# CVTOP.net
KiCad netlist of a schematic drawn in Altium Designer
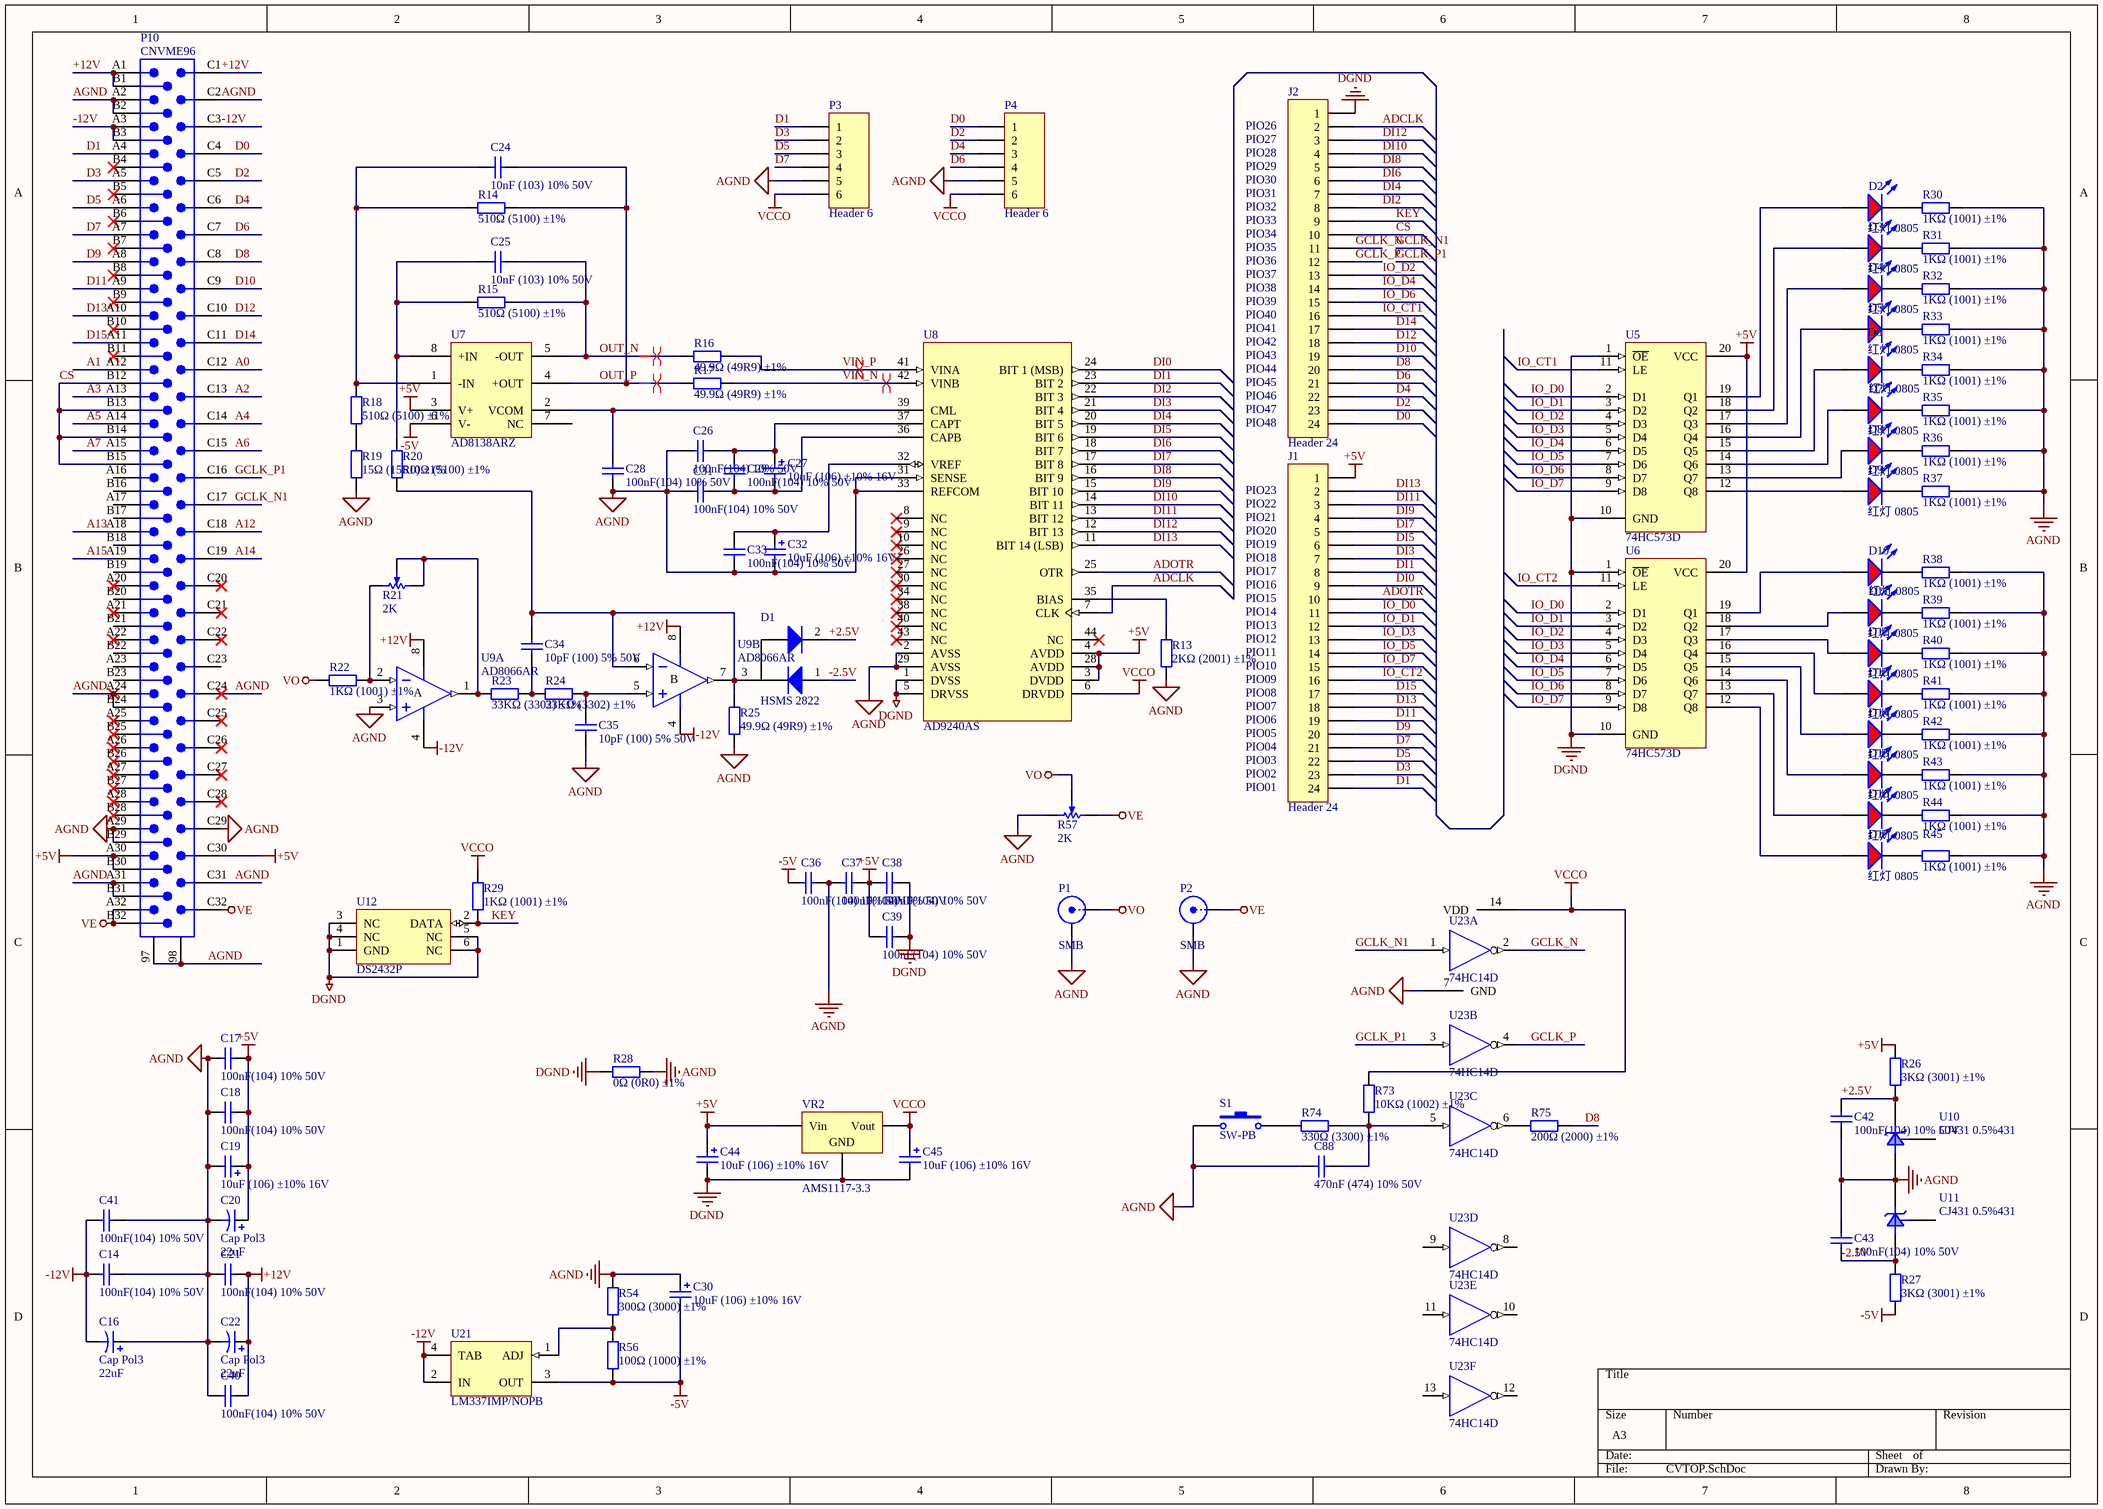
[diagram p0: CVTOP.SchDoc]

(export (version "E")
  (design (tool "Eeschema 10.0.6"))
  (components
    (comp (ref "C14")
      (value "100nF(104) 10% 50V")
      (footprint "LC-0805_C")
      (description "贴片电容")
      (libsource (lib "Miscellaneous Devices LC") (part "0805 100nF(104) 10% 50V"))
    )
    (comp (ref "C16")
      (value "Cap Pol3")
      (footprint "C2225")
      (description "Polarized Capacitor (Surface Mount)")
      (fields (field (name "ALTIUM_VALUE") "22uF") (field (name "PUBLISHER") "Altium Limited"))
      (libsource (lib "Miscellaneous Devices") (part "Cap Pol3"))
    )
    (comp (ref "C17")
      (value "100nF(104) 10% 50V")
      (footprint "LC-0805_C")
      (description "贴片电容")
      (libsource (lib "Miscellaneous Devices LC") (part "0805 100nF(104) 10% 50V"))
    )
    (comp (ref "C18")
      (value "100nF(104) 10% 50V")
      (footprint "LC-0805_C")
      (description "贴片电容")
      (libsource (lib "Miscellaneous Devices LC") (part "0805 100nF(104) 10% 50V"))
    )
    (comp (ref "C19")
      (value "10uF (106) ±10% 16V")
      (footprint "LC-CASE-A_3216")
      (description "钽电容")
      (libsource (lib "Miscellaneous Devices LC") (part "3216 10uF (106) 10% 16V"))
    )
    (comp (ref "C20")
      (value "Cap Pol3")
      (footprint "C2225")
      (description "Polarized Capacitor (Surface Mount)")
      (fields (field (name "ALTIUM_VALUE") "22uF") (field (name "PUBLISHER") "Altium Limited"))
      (libsource (lib "Miscellaneous Devices") (part "Cap Pol3"))
    )
    (comp (ref "C21")
      (value "100nF(104) 10% 50V")
      (footprint "LC-0805_C")
      (description "贴片电容")
      (libsource (lib "Miscellaneous Devices LC") (part "0805 100nF(104) 10% 50V"))
    )
    (comp (ref "C22")
      (value "Cap Pol3")
      (footprint "C2225")
      (description "Polarized Capacitor (Surface Mount)")
      (fields (field (name "ALTIUM_VALUE") "22uF") (field (name "PUBLISHER") "Altium Limited"))
      (libsource (lib "Miscellaneous Devices") (part "Cap Pol3"))
    )
    (comp (ref "C24")
      (value "10nF (103) 10% 50V")
      (footprint "LC-0805_C")
      (description "贴片电容")
      (libsource (lib "Miscellaneous Devices LC") (part "0805 10nF (103) 10% 50V"))
    )
    (comp (ref "C25")
      (value "10nF (103) 10% 50V")
      (footprint "LC-0805_C")
      (description "贴片电容")
      (libsource (lib "Miscellaneous Devices LC") (part "0805 10nF (103) 10% 50V"))
    )
    (comp (ref "C26")
      (value "100nF(104) 10% 50V")
      (footprint "LC-0805_C")
      (description "贴片电容")
      (libsource (lib "Miscellaneous Devices LC") (part "0805 100nF(104) 10% 50V"))
    )
    (comp (ref "C27")
      (value "10uF (106) ±10% 16V")
      (footprint "LC-CASE-A_3216")
      (description "钽电容")
      (libsource (lib "Miscellaneous Devices LC") (part "3216 10uF (106) 10% 16V"))
    )
    (comp (ref "C28")
      (value "100nF(104) 10% 50V")
      (footprint "LC-0805_C")
      (description "贴片电容")
      (libsource (lib "Miscellaneous Devices LC") (part "0805 100nF(104) 10% 50V"))
    )
    (comp (ref "C29")
      (value "100nF(104) 10% 50V")
      (footprint "LC-0805_C")
      (description "贴片电容")
      (libsource (lib "Miscellaneous Devices LC") (part "0805 100nF(104) 10% 50V"))
    )
    (comp (ref "C30")
      (value "10uF (106) ±10% 16V")
      (footprint "LC-CASE-A_3216")
      (description "钽电容")
      (libsource (lib "Miscellaneous Devices LC") (part "3216 10uF (106) 10% 16V"))
    )
    (comp (ref "C31")
      (value "100nF(104) 10% 50V")
      (footprint "LC-0805_C")
      (description "贴片电容")
      (libsource (lib "Miscellaneous Devices LC") (part "0805 100nF(104) 10% 50V"))
    )
    (comp (ref "C32")
      (value "10uF (106) ±10% 16V")
      (footprint "LC-CASE-A_3216")
      (description "钽电容")
      (libsource (lib "Miscellaneous Devices LC") (part "3216 10uF (106) 10% 16V"))
    )
    (comp (ref "C33")
      (value "100nF(104) 10% 50V")
      (footprint "LC-0805_C")
      (description "贴片电容")
      (libsource (lib "Miscellaneous Devices LC") (part "0805 100nF(104) 10% 50V"))
    )
    (comp (ref "C34")
      (value "10pF (100) 5% 50V")
      (footprint "LC-0805_C")
      (description "贴片电容")
      (libsource (lib "Miscellaneous Devices LC") (part "0805 10pF (100) 5% 50V"))
    )
    (comp (ref "C35")
      (value "10pF (100) 5% 50V")
      (footprint "LC-0805_C")
      (description "贴片电容")
      (libsource (lib "Miscellaneous Devices LC") (part "0805 10pF (100) 5% 50V"))
    )
    (comp (ref "C36")
      (value "100nF(104) 10% 50V")
      (footprint "LC-0805_C")
      (description "贴片电容")
      (libsource (lib "Miscellaneous Devices LC") (part "0805 100nF(104) 10% 50V"))
    )
    (comp (ref "C37")
      (value "100nF(104) 10% 50V")
      (footprint "LC-0805_C")
      (description "贴片电容")
      (libsource (lib "Miscellaneous Devices LC") (part "0805 100nF(104) 10% 50V"))
    )
    (comp (ref "C38")
      (value "100nF(104) 10% 50V")
      (footprint "LC-0805_C")
      (description "贴片电容")
      (libsource (lib "Miscellaneous Devices LC") (part "0805 100nF(104) 10% 50V"))
    )
    (comp (ref "C39")
      (value "100nF(104) 10% 50V")
      (footprint "LC-0805_C")
      (description "贴片电容")
      (libsource (lib "Miscellaneous Devices LC") (part "0805 100nF(104) 10% 50V"))
    )
    (comp (ref "C40")
      (value "100nF(104) 10% 50V")
      (footprint "LC-0805_C")
      (description "贴片电容")
      (libsource (lib "Miscellaneous Devices LC") (part "0805 100nF(104) 10% 50V"))
    )
    (comp (ref "C41")
      (value "100nF(104) 10% 50V")
      (footprint "LC-0805_C")
      (description "贴片电容")
      (libsource (lib "Miscellaneous Devices LC") (part "0805 100nF(104) 10% 50V"))
    )
    (comp (ref "C42")
      (value "100nF(104) 10% 50V")
      (footprint "LC-0805_C")
      (description "贴片电容")
      (libsource (lib "Miscellaneous Devices LC") (part "0805 100nF(104) 10% 50V"))
    )
    (comp (ref "C43")
      (value "100nF(104) 10% 50V")
      (footprint "LC-0805_C")
      (description "贴片电容")
      (libsource (lib "Miscellaneous Devices LC") (part "0805 100nF(104) 10% 50V"))
    )
    (comp (ref "C44")
      (value "10uF (106) ±10% 16V")
      (footprint "LC-CASE-A_3216")
      (description "钽电容")
      (libsource (lib "Miscellaneous Devices LC") (part "3216 10uF (106) 10% 16V"))
    )
    (comp (ref "C45")
      (value "10uF (106) ±10% 16V")
      (footprint "LC-CASE-A_3216")
      (description "钽电容")
      (libsource (lib "Miscellaneous Devices LC") (part "3216 10uF (106) 10% 16V"))
    )
    (comp (ref "C88")
      (value "470nF (474) 10% 50V")
      (footprint "LC-0805_C")
      (description "贴片电容")
      (libsource (lib "Miscellaneous Devices LC") (part "0805 470nF (474) 10% 50V"))
    )
    (comp (ref "D1")
      (value "HSMS 2822")
      (footprint "LC-SOT-23(SOT-23-3)")
      (description "开关二极管")
      (libsource (lib "Miscellaneous Devices LC") (part "SOT-23 BAV99 A7W"))
    )
    (comp (ref "D2")
      (value "红灯 0805")
      (footprint "LC-0805_LED_S1")
      (description "发光二极管")
      (libsource (lib "Miscellaneous Devices LC") (part "0805 红灯"))
    )
    (comp (ref "D3")
      (value "红灯 0805")
      (footprint "LC-0805_LED_S1")
      (description "发光二极管")
      (libsource (lib "Miscellaneous Devices LC") (part "0805 红灯"))
    )
    (comp (ref "D4")
      (value "红灯 0805")
      (footprint "LC-0805_LED_S1")
      (description "发光二极管")
      (libsource (lib "Miscellaneous Devices LC") (part "0805 红灯"))
    )
    (comp (ref "D5")
      (value "红灯 0805")
      (footprint "LC-0805_LED_S1")
      (description "发光二极管")
      (libsource (lib "Miscellaneous Devices LC") (part "0805 红灯"))
    )
    (comp (ref "D6")
      (value "红灯 0805")
      (footprint "LC-0805_LED_S1")
      (description "发光二极管")
      (libsource (lib "Miscellaneous Devices LC") (part "0805 红灯"))
    )
    (comp (ref "D7")
      (value "红灯 0805")
      (footprint "LC-0805_LED_S1")
      (description "发光二极管")
      (libsource (lib "Miscellaneous Devices LC") (part "0805 红灯"))
    )
    (comp (ref "D8")
      (value "红灯 0805")
      (footprint "LC-0805_LED_S1")
      (description "发光二极管")
      (libsource (lib "Miscellaneous Devices LC") (part "0805 红灯"))
    )
    (comp (ref "D9")
      (value "红灯 0805")
      (footprint "LC-0805_LED_S1")
      (description "发光二极管")
      (libsource (lib "Miscellaneous Devices LC") (part "0805 红灯"))
    )
    (comp (ref "D10")
      (value "红灯 0805")
      (footprint "LC-0805_LED_S1")
      (description "发光二极管")
      (libsource (lib "Miscellaneous Devices LC") (part "0805 红灯"))
    )
    (comp (ref "D11")
      (value "红灯 0805")
      (footprint "LC-0805_LED_S1")
      (description "发光二极管")
      (libsource (lib "Miscellaneous Devices LC") (part "0805 红灯"))
    )
    (comp (ref "D12")
      (value "红灯 0805")
      (footprint "LC-0805_LED_S1")
      (description "发光二极管")
      (libsource (lib "Miscellaneous Devices LC") (part "0805 红灯"))
    )
    (comp (ref "D13")
      (value "红灯 0805")
      (footprint "LC-0805_LED_S1")
      (description "发光二极管")
      (libsource (lib "Miscellaneous Devices LC") (part "0805 红灯"))
    )
    (comp (ref "D14")
      (value "红灯 0805")
      (footprint "LC-0805_LED_S1")
      (description "发光二极管")
      (libsource (lib "Miscellaneous Devices LC") (part "0805 红灯"))
    )
    (comp (ref "D15")
      (value "红灯 0805")
      (footprint "LC-0805_LED_S1")
      (description "发光二极管")
      (libsource (lib "Miscellaneous Devices LC") (part "0805 红灯"))
    )
    (comp (ref "D16")
      (value "红灯 0805")
      (footprint "LC-0805_LED_S1")
      (description "发光二极管")
      (libsource (lib "Miscellaneous Devices LC") (part "0805 红灯"))
    )
    (comp (ref "D17")
      (value "红灯 0805")
      (footprint "LC-0805_LED_S1")
      (description "发光二极管")
      (libsource (lib "Miscellaneous Devices LC") (part "0805 红灯"))
    )
    (comp (ref "J1")
      (value "Header 24")
      (footprint "HDR1X24")
      (description "Header, 24-Pin")
      (fields (field (name "PUBLISHER") "Altium Limited"))
      (libsource (lib "Miscellaneous Connectors") (part "Header 24"))
    )
    (comp (ref "J2")
      (value "Header 24")
      (footprint "HDR1X24")
      (description "Header, 24-Pin")
      (fields (field (name "PUBLISHER") "Altium Limited"))
      (libsource (lib "Miscellaneous Connectors") (part "Header 24"))
    )
    (comp (ref "P1")
      (value "SMB")
      (footprint "SMB_V-RJ45")
      (description "SMB Straight Connector")
      (fields (field (name "PUBLISHER") "Altium Limited"))
      (libsource (lib "Miscellaneous Connectors") (part "SMB"))
    )
    (comp (ref "P2")
      (value "SMB")
      (footprint "SMB_V-RJ45")
      (description "SMB Straight Connector")
      (fields (field (name "PUBLISHER") "Altium Limited"))
      (libsource (lib "Miscellaneous Connectors") (part "SMB"))
    )
    (comp (ref "P3")
      (value "Header 6")
      (footprint "HDR1X6")
      (description "Header, 6-Pin")
      (fields (field (name "PUBLISHER") "Altium Limited"))
      (libsource (lib "Miscellaneous Connectors") (part "Header 6"))
    )
    (comp (ref "P4")
      (value "Header 6")
      (footprint "HDR1X6")
      (description "Header, 6-Pin")
      (fields (field (name "PUBLISHER") "Altium Limited"))
      (libsource (lib "Miscellaneous Connectors") (part "Header 6"))
    )
    (comp (ref "P10")
      (value "CNVME96")
      (footprint "CNVME96")
      (description "96-Pin Connector (3x32 2.54mm grid)")
      (libsource (lib "*") (part "CNVME96"))
    )
    (comp (ref "R13")
      (value "2KΩ (2001) ±1%")
      (footprint "LC-0805_R")
      (description "贴片电阻")
      (libsource (lib "Miscellaneous Devices LC") (part "0805 2KΩ (2001) 1%"))
    )
    (comp (ref "R14")
      (value "510Ω (5100) ±1%")
      (footprint "LC-0805_R")
      (description "贴片电阻")
      (libsource (lib "Miscellaneous Devices LC") (part "0805 510Ω (5100) 1%"))
    )
    (comp (ref "R15")
      (value "510Ω (5100) ±1%")
      (footprint "LC-0805_R")
      (description "贴片电阻")
      (libsource (lib "Miscellaneous Devices LC") (part "0805 510Ω (5100) 1%"))
    )
    (comp (ref "R16")
      (value "49.9Ω (49R9) ±1%")
      (footprint "LC-0805_R")
      (description "贴片电阻")
      (libsource (lib "Miscellaneous Devices LC") (part "0805 49.9Ω (49R9) 1%"))
    )
    (comp (ref "R17")
      (value "49.9Ω (49R9) ±1%")
      (footprint "LC-0805_R")
      (description "贴片电阻")
      (libsource (lib "Miscellaneous Devices LC") (part "0805 49.9Ω (49R9) 1%"))
    )
    (comp (ref "R18")
      (value "510Ω (5100) ±1%")
      (footprint "LC-0805_R")
      (description "贴片电阻")
      (libsource (lib "") (part "0805 510Ω (5100) 1%_1"))
    )
    (comp (ref "R19")
      (value "15Ω (15R0) ±1%")
      (footprint "LC-0805_R")
      (description "贴片电阻")
      (libsource (lib "Miscellaneous Devices LC") (part "0805 15Ω (15R0) 1%"))
    )
    (comp (ref "R20")
      (value "510Ω (5100) ±1%")
      (footprint "LC-0805_R")
      (description "贴片电阻")
      (libsource (lib "") (part "0805 510Ω (5100) 1%_1"))
    )
    (comp (ref "R21")
      (value "2K")
      (footprint "POT4MM-2")
      (description "Square Trimming Potentiometer")
      (fields (field (name "PUBLISHER") "Altium Limited"))
      (libsource (lib "Miscellaneous Devices") (part "RPot SM"))
    )
    (comp (ref "R22")
      (value "1KΩ (1001) ±1%")
      (footprint "LC-0805_R")
      (description "贴片电阻")
      (libsource (lib "Miscellaneous Devices LC") (part "0805 1KΩ (1001) 1%"))
    )
    (comp (ref "R23")
      (value "33KΩ (3302) ±1%")
      (footprint "LC-0805_R")
      (description "贴片电阻")
      (libsource (lib "Miscellaneous Devices LC") (part "0805 33KΩ (3302) 1%"))
    )
    (comp (ref "R24")
      (value "33KΩ (3302) ±1%")
      (footprint "LC-0805_R")
      (description "贴片电阻")
      (libsource (lib "Miscellaneous Devices LC") (part "0805 33KΩ (3302) 1%"))
    )
    (comp (ref "R25")
      (value "49.9Ω (49R9) ±1%")
      (footprint "LC-0805_R")
      (description "贴片电阻")
      (libsource (lib "") (part "0805 49.9Ω (49R9) 1%_1"))
    )
    (comp (ref "R26")
      (value "3KΩ (3001) ±1%")
      (footprint "LC-0805_R")
      (description "贴片电阻")
      (libsource (lib "Miscellaneous Devices LC") (part "0805 3KΩ (3001) 1%"))
    )
    (comp (ref "R27")
      (value "3KΩ (3001) ±1%")
      (footprint "LC-0805_R")
      (description "贴片电阻")
      (libsource (lib "Miscellaneous Devices LC") (part "0805 3KΩ (3001) 1%"))
    )
    (comp (ref "R28")
      (value "0Ω (0R0) ±1%")
      (footprint "LC-0805_R")
      (description "贴片电阻")
      (libsource (lib "Miscellaneous Devices LC") (part "0805 0Ω (0R0) 1%"))
    )
    (comp (ref "R29")
      (value "1KΩ (1001) ±1%")
      (footprint "LC-0805_R")
      (description "贴片电阻")
      (libsource (lib "") (part "0805 1KΩ (1001) 1%_1"))
    )
    (comp (ref "R30")
      (value "1KΩ (1001) ±1%")
      (footprint "LC-0805_R")
      (description "贴片电阻")
      (libsource (lib "Miscellaneous Devices LC") (part "0805 1KΩ (1001) 1%"))
    )
    (comp (ref "R31")
      (value "1KΩ (1001) ±1%")
      (footprint "LC-0805_R")
      (description "贴片电阻")
      (libsource (lib "Miscellaneous Devices LC") (part "0805 1KΩ (1001) 1%"))
    )
    (comp (ref "R32")
      (value "1KΩ (1001) ±1%")
      (footprint "LC-0805_R")
      (description "贴片电阻")
      (libsource (lib "Miscellaneous Devices LC") (part "0805 1KΩ (1001) 1%"))
    )
    (comp (ref "R33")
      (value "1KΩ (1001) ±1%")
      (footprint "LC-0805_R")
      (description "贴片电阻")
      (libsource (lib "Miscellaneous Devices LC") (part "0805 1KΩ (1001) 1%"))
    )
    (comp (ref "R34")
      (value "1KΩ (1001) ±1%")
      (footprint "LC-0805_R")
      (description "贴片电阻")
      (libsource (lib "Miscellaneous Devices LC") (part "0805 1KΩ (1001) 1%"))
    )
    (comp (ref "R35")
      (value "1KΩ (1001) ±1%")
      (footprint "LC-0805_R")
      (description "贴片电阻")
      (libsource (lib "Miscellaneous Devices LC") (part "0805 1KΩ (1001) 1%"))
    )
    (comp (ref "R36")
      (value "1KΩ (1001) ±1%")
      (footprint "LC-0805_R")
      (description "贴片电阻")
      (libsource (lib "Miscellaneous Devices LC") (part "0805 1KΩ (1001) 1%"))
    )
    (comp (ref "R37")
      (value "1KΩ (1001) ±1%")
      (footprint "LC-0805_R")
      (description "贴片电阻")
      (libsource (lib "Miscellaneous Devices LC") (part "0805 1KΩ (1001) 1%"))
    )
    (comp (ref "R38")
      (value "1KΩ (1001) ±1%")
      (footprint "LC-0805_R")
      (description "贴片电阻")
      (libsource (lib "Miscellaneous Devices LC") (part "0805 1KΩ (1001) 1%"))
    )
    (comp (ref "R39")
      (value "1KΩ (1001) ±1%")
      (footprint "LC-0805_R")
      (description "贴片电阻")
      (libsource (lib "Miscellaneous Devices LC") (part "0805 1KΩ (1001) 1%"))
    )
    (comp (ref "R40")
      (value "1KΩ (1001) ±1%")
      (footprint "LC-0805_R")
      (description "贴片电阻")
      (libsource (lib "Miscellaneous Devices LC") (part "0805 1KΩ (1001) 1%"))
    )
    (comp (ref "R41")
      (value "1KΩ (1001) ±1%")
      (footprint "LC-0805_R")
      (description "贴片电阻")
      (libsource (lib "Miscellaneous Devices LC") (part "0805 1KΩ (1001) 1%"))
    )
    (comp (ref "R42")
      (value "1KΩ (1001) ±1%")
      (footprint "LC-0805_R")
      (description "贴片电阻")
      (libsource (lib "Miscellaneous Devices LC") (part "0805 1KΩ (1001) 1%"))
    )
    (comp (ref "R43")
      (value "1KΩ (1001) ±1%")
      (footprint "LC-0805_R")
      (description "贴片电阻")
      (libsource (lib "Miscellaneous Devices LC") (part "0805 1KΩ (1001) 1%"))
    )
    (comp (ref "R44")
      (value "1KΩ (1001) ±1%")
      (footprint "LC-0805_R")
      (description "贴片电阻")
      (libsource (lib "Miscellaneous Devices LC") (part "0805 1KΩ (1001) 1%"))
    )
    (comp (ref "R45")
      (value "1KΩ (1001) ±1%")
      (footprint "LC-0805_R")
      (description "贴片电阻")
      (libsource (lib "Miscellaneous Devices LC") (part "0805 1KΩ (1001) 1%"))
    )
    (comp (ref "R54")
      (value "300Ω (3000) ±1%")
      (footprint "LC-0805_R")
      (description "贴片电阻")
      (libsource (lib "Miscellaneous Devices LC") (part "0805 300Ω (3000) 1%"))
    )
    (comp (ref "R56")
      (value "100Ω (1000) ±1%")
      (footprint "LC-0805_R")
      (description "贴片电阻")
      (libsource (lib "Miscellaneous Devices LC") (part "0805 100Ω (1000) 1%"))
    )
    (comp (ref "R57")
      (value "2K")
      (footprint "POT4MM-2")
      (description "Square Trimming Potentiometer")
      (fields (field (name "PUBLISHER") "Altium Limited"))
      (libsource (lib "Miscellaneous Devices") (part "RPot SM"))
    )
    (comp (ref "R73")
      (value "10KΩ (1002) ±1%")
      (footprint "LC-0805_R")
      (description "贴片电阻")
      (libsource (lib "Miscellaneous Devices LC") (part "0805 10KΩ (1002) 1%"))
    )
    (comp (ref "R74")
      (value "330Ω (3300) ±1%")
      (footprint "LC-0805_R")
      (description "贴片电阻")
      (libsource (lib "Miscellaneous Devices LC") (part "0805 330Ω (3300) 1%"))
    )
    (comp (ref "R75")
      (value "200Ω (2000) ±1%")
      (footprint "LC-0805_R")
      (description "贴片电阻")
      (libsource (lib "Miscellaneous Devices LC") (part "0805 200Ω (2000) 1%"))
    )
    (comp (ref "S1")
      (value "SW-PB")
      (footprint "SPST-2")
      (description "Switch")
      (fields (field (name "PUBLISHER") "Altium Limited"))
      (libsource (lib "Miscellaneous Devices") (part "SW-PB"))
    )
    (comp (ref "U5")
      (value "74HC573D")
      (footprint "LC-SOIC-20_300mil")
      (description "74系列逻辑芯片")
      (libsource (lib "Miscellaneous Devices LC") (part "74HC573D"))
    )
    (comp (ref "U6")
      (value "74HC573D")
      (footprint "LC-SOIC-20_300mil")
      (description "74系列逻辑芯片")
      (libsource (lib "Miscellaneous Devices LC") (part "74HC573D"))
    )
    (comp (ref "U7") (value "AD8138ARZ") (footprint "SO-8_N") (libsource (lib "AD8138") (part "AD8138ARZ")))
    (comp (ref "U8")
      (value "AD9240AS")
      (footprint "S-44-MQFP_N")
      (description "Complete 14-Bit, 10 MSPS Monolithic A/D Converter, 44-Pin MQFP, Industrial")
      (fields (field (name "PUBLISHER") "Altium Limited"))
      (libsource (lib "AD Converter Analog to Digital") (part "AD9240AS"))
    )
    (comp (ref "U9")
      (value "AD8066AR")
      (footprint "mini-ET:SO-8_N")
      (description "Low Cost, 300MHz Voltage Feedback Amplifier")
      (fields (field (name "PUBLISHER") "Altium Limited"))
      (libsource (lib "AD Operational Amplifier") (part "AD8056AR"))
    )
    (comp (ref "U10")
      (value "CJ431 0.5%431")
      (footprint "LC-SOT-23(SOT-23-3)")
      (description "电压基准")
      (libsource (lib "Miscellaneous Devices LC") (part "CJ431 0.5%431"))
    )
    (comp (ref "U11")
      (value "CJ431 0.5%431")
      (footprint "LC-SOT-23(SOT-23-3)")
      (description "电压基准")
      (libsource (lib "Miscellaneous Devices LC") (part "CJ431 0.5%431"))
    )
    (comp (ref "U12")
      (value "DS2432P")
      (footprint "TSOC6")
      (description "256-Bit 1-Wire EEPROM")
      (fields (field (name "PUBLISHER") "Altium Limited"))
      (libsource (lib "Dallas Memory EEPROM") (part "DS2430AP"))
    )
    (comp (ref "U21")
      (value "LM337IMP/NOPB")
      (footprint "MP04A_N")
      (description "3-Terminal Adjustable Negative Regulator, 4-pin SOT-223, Pb-Free")
      (fields
        (field (name "MANUFACTURER") "National Semiconductor")
        (field (name "PUBLISHER") "Altium Limited")
      )
      (libsource (lib "NSC LDO") (part "LM337IMP/NOPB"))
    )
    (comp (ref "U23")
      (value "74HC14D")
      (footprint "LC-SOIC-14_150mil")
      (description "74系列逻辑芯片")
      (libsource (lib "Miscellaneous Devices LC") (part "74HC14D_[C5605]"))
    )
    (comp (ref "VR2")
      (value "AMS1117-3.3")
      (footprint "LC-SOT-223")
      (description "低压差线性稳压(LDO)")
      (libsource (lib "Miscellaneous Devices LC") (part "SOT-223 AMS1117-3.3"))
    )
  )
  (nets
    (net (code "1") (name "+5V") (class "Default")
      (node (ref "C17") (pin "2") (pinfunction "2_2") (pintype "passive"))
      (node (ref "C18") (pin "2") (pinfunction "2_2") (pintype "passive"))
      (node (ref "C19") (pin "1") (pinfunction "1_1") (pintype "passive"))
      (node (ref "C20") (pin "1") (pinfunction "1_1") (pintype "passive"))
      (node (ref "C37") (pin "1") (pinfunction "1_1") (pintype "passive"))
      (node (ref "C38") (pin "2") (pinfunction "2_2") (pintype "passive"))
      (node (ref "C39") (pin "2") (pinfunction "2_2") (pintype "passive"))
      (node (ref "C44") (pin "1") (pinfunction "1_1") (pintype "passive"))
      (node (ref "J1") (pin "1") (pinfunction "1_1") (pintype "passive"))
      (node (ref "P10") (pin "A30") (pinfunction "A30_A30") (pintype "passive"))
      (node (ref "P10") (pin "B30") (pinfunction "B30_B30") (pintype "passive"))
      (node (ref "P10") (pin "C30") (pinfunction "C30_C30") (pintype "passive"))
      (node (ref "R26") (pin "2") (pinfunction "2_2") (pintype "passive"))
      (node (ref "U5") (pin "20") (pinfunction "VCC_20") (pintype "power_in"))
      (node (ref "U6") (pin "20") (pinfunction "VCC_20") (pintype "power_in"))
      (node (ref "U7") (pin "3") (pinfunction "V+_3") (pintype "passive"))
      (node (ref "U8") (pin "28") (pinfunction "AVDD_28") (pintype "power_in"))
      (node (ref "U8") (pin "3") (pinfunction "DVDD_3") (pintype "power_in"))
      (node (ref "U8") (pin "4") (pinfunction "AVDD_4") (pintype "power_in"))
      (node (ref "VR2") (pin "3") (pinfunction "Vin_3") (pintype "passive"))
    )
    (net (code "2") (name "+12V") (class "Default")
      (node (ref "C21") (pin "2") (pinfunction "2_2") (pintype "passive"))
      (node (ref "C22") (pin "1") (pinfunction "1_1") (pintype "passive"))
      (node (ref "C40") (pin "1") (pinfunction "1_1") (pintype "passive"))
      (node (ref "P10") (pin "A1") (pinfunction "A1_A1") (pintype "passive"))
      (node (ref "P10") (pin "B1") (pinfunction "B1_B1") (pintype "passive"))
      (node (ref "P10") (pin "C1") (pinfunction "C1_C1") (pintype "passive"))
      (node (ref "U9") (pin "8") (pinfunction "V+_8") (pintype "power_in"))
    )
    (net (code "3") (name "-5V") (class "Default")
      (node (ref "C30") (pin "2") (pinfunction "2_2") (pintype "passive"))
      (node (ref "C36") (pin "2") (pinfunction "2_2") (pintype "passive"))
      (node (ref "R27") (pin "1") (pinfunction "1_1") (pintype "passive"))
      (node (ref "R56") (pin "1") (pinfunction "1_1") (pintype "passive"))
      (node (ref "U21") (pin "3") (pinfunction "OUT_3") (pintype "power_in"))
      (node (ref "U7") (pin "6") (pinfunction "V-_6") (pintype "passive"))
    )
    (net (code "4") (name "-12V") (class "Default")
      (node (ref "C14") (pin "1") (pinfunction "1_1") (pintype "passive"))
      (node (ref "C16") (pin "2") (pinfunction "2_2") (pintype "passive"))
      (node (ref "C41") (pin "2") (pinfunction "2_2") (pintype "passive"))
      (node (ref "P10") (pin "A3") (pinfunction "A3_A3") (pintype "passive"))
      (node (ref "P10") (pin "B3") (pinfunction "B3_B3") (pintype "passive"))
      (node (ref "P10") (pin "C3") (pinfunction "C3_C3") (pintype "passive"))
      (node (ref "U21") (pin "2") (pinfunction "IN_2") (pintype "power_in"))
      (node (ref "U21") (pin "4") (pinfunction "TAB_4") (pintype "power_in"))
      (node (ref "U9") (pin "4") (pinfunction "V-_4") (pintype "power_in"))
    )
    (net (code "5") (name "/+2.5V") (class "Default")
      (node (ref "C42") (pin "1") (pinfunction "1_1") (pintype "passive"))
      (node (ref "D1") (pin "2") (pinfunction "A_2") (pintype "passive"))
      (node (ref "R26") (pin "1") (pinfunction "1_1") (pintype "passive"))
      (node (ref "U10") (pin "2") (pinfunction "K_2") (pintype "passive"))
    )
    (net (code "6") (name "/-2.5V") (class "Default")
      (node (ref "C43") (pin "2") (pinfunction "2_2") (pintype "passive"))
      (node (ref "D1") (pin "1") (pinfunction "A_1") (pintype "passive"))
      (node (ref "R27") (pin "2") (pinfunction "2_2") (pintype "passive"))
      (node (ref "U11") (pin "3") (pinfunction "A_3") (pintype "passive"))
    )
    (net (code "7") (name "/A0") (class "Default")
      (node (ref "P10") (pin "C12") (pinfunction "C12_C12") (pintype "passive"))
    )
    (net (code "8") (name "/A1") (class "Default")
      (node (ref "P10") (pin "A12") (pinfunction "A12_A12") (pintype "passive"))
    )
    (net (code "9") (name "/A2") (class "Default")
      (node (ref "P10") (pin "C13") (pinfunction "C13_C13") (pintype "passive"))
    )
    (net (code "10") (name "/A3") (class "Default")
      (node (ref "P10") (pin "A13") (pinfunction "A13_A13") (pintype "passive"))
    )
    (net (code "11") (name "/A4") (class "Default")
      (node (ref "P10") (pin "C14") (pinfunction "C14_C14") (pintype "passive"))
    )
    (net (code "12") (name "/A5") (class "Default")
      (node (ref "P10") (pin "A14") (pinfunction "A14_A14") (pintype "passive"))
    )
    (net (code "13") (name "/A6") (class "Default")
      (node (ref "P10") (pin "C15") (pinfunction "C15_C15") (pintype "passive"))
    )
    (net (code "14") (name "/A7") (class "Default")
      (node (ref "P10") (pin "A15") (pinfunction "A15_A15") (pintype "passive"))
    )
    (net (code "15") (name "/A12") (class "Default")
      (node (ref "P10") (pin "C18") (pinfunction "C18_C18") (pintype "passive"))
    )
    (net (code "16") (name "/A13") (class "Default")
      (node (ref "P10") (pin "A18") (pinfunction "A18_A18") (pintype "passive"))
    )
    (net (code "17") (name "/A14") (class "Default")
      (node (ref "P10") (pin "C19") (pinfunction "C19_C19") (pintype "passive"))
    )
    (net (code "18") (name "/A15") (class "Default")
      (node (ref "P10") (pin "A19") (pinfunction "A19_A19") (pintype "passive"))
    )
    (net (code "19") (name "/ADCLK") (class "Default")
      (node (ref "J2") (pin "2") (pinfunction "2_2") (pintype "passive"))
      (node (ref "U8") (pin "7") (pinfunction "CLK_7") (pintype "input"))
    )
    (net (code "20") (name "/ADOTR") (class "Default")
      (node (ref "J1") (pin "10") (pinfunction "10_10") (pintype "passive"))
      (node (ref "U8") (pin "25") (pinfunction "OTR_25") (pintype "output"))
    )
    (net (code "21") (name "/CS") (class "Default")
      (node (ref "J2") (pin "10") (pinfunction "10_10") (pintype "passive"))
      (node (ref "P10") (pin "B12") (pinfunction "B12_B12") (pintype "passive"))
      (node (ref "P10") (pin "B13") (pinfunction "B13_B13") (pintype "passive"))
      (node (ref "P10") (pin "B14") (pinfunction "B14_B14") (pintype "passive"))
      (node (ref "P10") (pin "B15") (pinfunction "B15_B15") (pintype "passive"))
    )
    (net (code "22") (name "/D0") (class "Default")
      (node (ref "J2") (pin "24") (pinfunction "24_24") (pintype "passive"))
      (node (ref "P10") (pin "C4") (pinfunction "C4_C4") (pintype "passive"))
      (node (ref "P4") (pin "1") (pinfunction "1_1") (pintype "passive"))
    )
    (net (code "23") (name "/D1") (class "Default")
      (node (ref "J1") (pin "24") (pinfunction "24_24") (pintype "passive"))
      (node (ref "P10") (pin "A4") (pinfunction "A4_A4") (pintype "passive"))
      (node (ref "P3") (pin "1") (pinfunction "1_1") (pintype "passive"))
    )
    (net (code "24") (name "/D2") (class "Default")
      (node (ref "J2") (pin "23") (pinfunction "23_23") (pintype "passive"))
      (node (ref "P10") (pin "C5") (pinfunction "C5_C5") (pintype "passive"))
      (node (ref "P4") (pin "2") (pinfunction "2_2") (pintype "passive"))
    )
    (net (code "25") (name "/D3") (class "Default")
      (node (ref "J1") (pin "23") (pinfunction "23_23") (pintype "passive"))
      (node (ref "P10") (pin "A5") (pinfunction "A5_A5") (pintype "passive"))
      (node (ref "P3") (pin "2") (pinfunction "2_2") (pintype "passive"))
    )
    (net (code "26") (name "/D4") (class "Default")
      (node (ref "J2") (pin "22") (pinfunction "22_22") (pintype "passive"))
      (node (ref "P10") (pin "C6") (pinfunction "C6_C6") (pintype "passive"))
      (node (ref "P4") (pin "3") (pinfunction "3_3") (pintype "passive"))
    )
    (net (code "27") (name "/D5") (class "Default")
      (node (ref "J1") (pin "22") (pinfunction "22_22") (pintype "passive"))
      (node (ref "P10") (pin "A6") (pinfunction "A6_A6") (pintype "passive"))
      (node (ref "P3") (pin "3") (pinfunction "3_3") (pintype "passive"))
    )
    (net (code "28") (name "/D6") (class "Default")
      (node (ref "J2") (pin "21") (pinfunction "21_21") (pintype "passive"))
      (node (ref "P10") (pin "C7") (pinfunction "C7_C7") (pintype "passive"))
      (node (ref "P4") (pin "4") (pinfunction "4_4") (pintype "passive"))
    )
    (net (code "29") (name "/D7") (class "Default")
      (node (ref "J1") (pin "21") (pinfunction "21_21") (pintype "passive"))
      (node (ref "P10") (pin "A7") (pinfunction "A7_A7") (pintype "passive"))
      (node (ref "P3") (pin "4") (pinfunction "4_4") (pintype "passive"))
    )
    (net (code "30") (name "/D8") (class "Default")
      (node (ref "J2") (pin "20") (pinfunction "20_20") (pintype "passive"))
      (node (ref "P10") (pin "C8") (pinfunction "C8_C8") (pintype "passive"))
      (node (ref "R75") (pin "2") (pinfunction "2_2") (pintype "passive"))
    )
    (net (code "31") (name "/D9") (class "Default")
      (node (ref "J1") (pin "20") (pinfunction "20_20") (pintype "passive"))
      (node (ref "P10") (pin "A8") (pinfunction "A8_A8") (pintype "passive"))
    )
    (net (code "32") (name "/D10") (class "Default")
      (node (ref "J2") (pin "19") (pinfunction "19_19") (pintype "passive"))
      (node (ref "P10") (pin "C9") (pinfunction "C9_C9") (pintype "passive"))
    )
    (net (code "33") (name "/D11") (class "Default")
      (node (ref "J1") (pin "19") (pinfunction "19_19") (pintype "passive"))
      (node (ref "P10") (pin "A9") (pinfunction "A9_A9") (pintype "passive"))
    )
    (net (code "34") (name "/D12") (class "Default")
      (node (ref "J2") (pin "18") (pinfunction "18_18") (pintype "passive"))
      (node (ref "P10") (pin "C10") (pinfunction "C10_C10") (pintype "passive"))
    )
    (net (code "35") (name "/D13") (class "Default")
      (node (ref "J1") (pin "18") (pinfunction "18_18") (pintype "passive"))
      (node (ref "P10") (pin "A10") (pinfunction "A10_A10") (pintype "passive"))
    )
    (net (code "36") (name "/D14") (class "Default")
      (node (ref "J2") (pin "17") (pinfunction "17_17") (pintype "passive"))
      (node (ref "P10") (pin "C11") (pinfunction "C11_C11") (pintype "passive"))
    )
    (net (code "37") (name "/D15") (class "Default")
      (node (ref "J1") (pin "17") (pinfunction "17_17") (pintype "passive"))
      (node (ref "P10") (pin "A11") (pinfunction "A11_A11") (pintype "passive"))
    )
    (net (code "38") (name "/DI0") (class "Default")
      (node (ref "J1") (pin "9") (pinfunction "9_9") (pintype "passive"))
      (node (ref "U8") (pin "24") (pinfunction "BIT_1_(MSB)_24") (pintype "output"))
    )
    (net (code "39") (name "/DI1") (class "Default")
      (node (ref "J1") (pin "8") (pinfunction "8_8") (pintype "passive"))
      (node (ref "U8") (pin "23") (pinfunction "BIT_2_23") (pintype "output"))
    )
    (net (code "40") (name "/DI2") (class "Default")
      (node (ref "J2") (pin "8") (pinfunction "8_8") (pintype "passive"))
      (node (ref "U8") (pin "22") (pinfunction "BIT_3_22") (pintype "output"))
    )
    (net (code "41") (name "/DI3") (class "Default")
      (node (ref "J1") (pin "7") (pinfunction "7_7") (pintype "passive"))
      (node (ref "U8") (pin "21") (pinfunction "BIT_4_21") (pintype "output"))
    )
    (net (code "42") (name "/DI4") (class "Default")
      (node (ref "J2") (pin "7") (pinfunction "7_7") (pintype "passive"))
      (node (ref "U8") (pin "20") (pinfunction "BIT_5_20") (pintype "output"))
    )
    (net (code "43") (name "/DI5") (class "Default")
      (node (ref "J1") (pin "6") (pinfunction "6_6") (pintype "passive"))
      (node (ref "U8") (pin "19") (pinfunction "BIT_6_19") (pintype "output"))
    )
    (net (code "44") (name "/DI6") (class "Default")
      (node (ref "J2") (pin "6") (pinfunction "6_6") (pintype "passive"))
      (node (ref "U8") (pin "18") (pinfunction "BIT_7_18") (pintype "output"))
    )
    (net (code "45") (name "/DI7") (class "Default")
      (node (ref "J1") (pin "5") (pinfunction "5_5") (pintype "passive"))
      (node (ref "U8") (pin "17") (pinfunction "BIT_8_17") (pintype "output"))
    )
    (net (code "46") (name "/DI8") (class "Default")
      (node (ref "J2") (pin "5") (pinfunction "5_5") (pintype "passive"))
      (node (ref "U8") (pin "16") (pinfunction "BIT_9_16") (pintype "output"))
    )
    (net (code "47") (name "/DI9") (class "Default")
      (node (ref "J1") (pin "4") (pinfunction "4_4") (pintype "passive"))
      (node (ref "U8") (pin "15") (pinfunction "BIT_10_15") (pintype "output"))
    )
    (net (code "48") (name "/DI10") (class "Default")
      (node (ref "J2") (pin "4") (pinfunction "4_4") (pintype "passive"))
      (node (ref "U8") (pin "14") (pinfunction "BIT_11_14") (pintype "output"))
    )
    (net (code "49") (name "/DI11") (class "Default")
      (node (ref "J1") (pin "3") (pinfunction "3_3") (pintype "passive"))
      (node (ref "U8") (pin "13") (pinfunction "BIT_12_13") (pintype "output"))
    )
    (net (code "50") (name "/DI12") (class "Default")
      (node (ref "J2") (pin "3") (pinfunction "3_3") (pintype "passive"))
      (node (ref "U8") (pin "12") (pinfunction "BIT_13_12") (pintype "output"))
    )
    (net (code "51") (name "/DI13") (class "Default")
      (node (ref "J1") (pin "2") (pinfunction "2_2") (pintype "passive"))
      (node (ref "U8") (pin "11") (pinfunction "BIT_14_(LSB)_11") (pintype "output"))
    )
    (net (code "52") (name "/GCLK_N") (class "Default")
      (node (ref "J2") (pin "11") (pinfunction "11_11") (pintype "passive"))
      (node (ref "U23") (pin "2") (pinfunction "Y_2") (pintype "output"))
    )
    (net (code "53") (name "/GCLK_N1") (class "Default")
      (node (ref "P10") (pin "C17") (pinfunction "C17_C17") (pintype "passive"))
      (node (ref "U23") (pin "1") (pinfunction "A_1") (pintype "input"))
    )
    (net (code "54") (name "/GCLK_P") (class "Default")
      (node (ref "J2") (pin "12") (pinfunction "12_12") (pintype "passive"))
      (node (ref "U23") (pin "4") (pinfunction "Y_4") (pintype "output"))
    )
    (net (code "55") (name "/GCLK_P1") (class "Default")
      (node (ref "P10") (pin "C16") (pinfunction "C16_C16") (pintype "passive"))
      (node (ref "U23") (pin "3") (pinfunction "A_3") (pintype "input"))
    )
    (net (code "56") (name "/IO_CT1") (class "Default")
      (node (ref "J2") (pin "16") (pinfunction "16_16") (pintype "passive"))
      (node (ref "U5") (pin "11") (pinfunction "LE_11") (pintype "input"))
    )
    (net (code "57") (name "/IO_CT2") (class "Default")
      (node (ref "J1") (pin "16") (pinfunction "16_16") (pintype "passive"))
      (node (ref "U6") (pin "11") (pinfunction "LE_11") (pintype "input"))
    )
    (net (code "58") (name "/IO_D0") (class "Default")
      (node (ref "J1") (pin "11") (pinfunction "11_11") (pintype "passive"))
      (node (ref "U5") (pin "2") (pinfunction "D1_2") (pintype "input"))
      (node (ref "U6") (pin "2") (pinfunction "D1_2") (pintype "input"))
    )
    (net (code "59") (name "/IO_D1") (class "Default")
      (node (ref "J1") (pin "12") (pinfunction "12_12") (pintype "passive"))
      (node (ref "U5") (pin "3") (pinfunction "D2_3") (pintype "input"))
      (node (ref "U6") (pin "3") (pinfunction "D2_3") (pintype "input"))
    )
    (net (code "60") (name "/IO_D2") (class "Default")
      (node (ref "J2") (pin "13") (pinfunction "13_13") (pintype "passive"))
      (node (ref "U5") (pin "4") (pinfunction "D3_4") (pintype "input"))
      (node (ref "U6") (pin "4") (pinfunction "D3_4") (pintype "input"))
    )
    (net (code "61") (name "/IO_D3") (class "Default")
      (node (ref "J1") (pin "13") (pinfunction "13_13") (pintype "passive"))
      (node (ref "U5") (pin "5") (pinfunction "D4_5") (pintype "input"))
      (node (ref "U6") (pin "5") (pinfunction "D4_5") (pintype "input"))
    )
    (net (code "62") (name "/IO_D4") (class "Default")
      (node (ref "J2") (pin "14") (pinfunction "14_14") (pintype "passive"))
      (node (ref "U5") (pin "6") (pinfunction "D5_6") (pintype "input"))
      (node (ref "U6") (pin "6") (pinfunction "D5_6") (pintype "input"))
    )
    (net (code "63") (name "/IO_D5") (class "Default")
      (node (ref "J1") (pin "14") (pinfunction "14_14") (pintype "passive"))
      (node (ref "U5") (pin "7") (pinfunction "D6_7") (pintype "input"))
      (node (ref "U6") (pin "7") (pinfunction "D6_7") (pintype "input"))
    )
    (net (code "64") (name "/IO_D6") (class "Default")
      (node (ref "J2") (pin "15") (pinfunction "15_15") (pintype "passive"))
      (node (ref "U5") (pin "8") (pinfunction "D7_8") (pintype "input"))
      (node (ref "U6") (pin "8") (pinfunction "D7_8") (pintype "input"))
    )
    (net (code "65") (name "/IO_D7") (class "Default")
      (node (ref "J1") (pin "15") (pinfunction "15_15") (pintype "passive"))
      (node (ref "U5") (pin "9") (pinfunction "D8_9") (pintype "input"))
      (node (ref "U6") (pin "9") (pinfunction "D8_9") (pintype "input"))
    )
    (net (code "66") (name "/KEY") (class "Default")
      (node (ref "J2") (pin "9") (pinfunction "9_9") (pintype "passive"))
      (node (ref "R29") (pin "1") (pinfunction "1_1") (pintype "passive"))
      (node (ref "U12") (pin "2") (pinfunction "DATA_2") (pintype "bidirectional"))
    )
    (net (code "67") (name "/OUT_N") (class "Default")
      (node (ref "C25") (pin "2") (pinfunction "2_2") (pintype "passive"))
      (node (ref "R15") (pin "2") (pinfunction "2_2") (pintype "passive"))
      (node (ref "R16") (pin "1") (pinfunction "1_1") (pintype "passive"))
      (node (ref "U7") (pin "5") (pinfunction "-OUT_5") (pintype "passive"))
    )
    (net (code "68") (name "/OUT_P") (class "Default")
      (node (ref "C24") (pin "2") (pinfunction "2_2") (pintype "passive"))
      (node (ref "R14") (pin "2") (pinfunction "2_2") (pintype "passive"))
      (node (ref "R17") (pin "1") (pinfunction "1_1") (pintype "passive"))
      (node (ref "U7") (pin "4") (pinfunction "+OUT_4") (pintype "passive"))
    )
    (net (code "69") (name "/VIN_N") (class "Default")
      (node (ref "R17") (pin "2") (pinfunction "2_2") (pintype "passive"))
      (node (ref "U8") (pin "42") (pinfunction "VINB_42") (pintype "input"))
    )
    (net (code "70") (name "/VIN_P") (class "Default")
      (node (ref "R16") (pin "2") (pinfunction "2_2") (pintype "passive"))
      (node (ref "U8") (pin "41") (pinfunction "VINA_41") (pintype "input"))
    )
    (net (code "71") (name "AGND") (class "Default")
      (node (ref "C14") (pin "2") (pinfunction "2_2") (pintype "passive"))
      (node (ref "C16") (pin "1") (pinfunction "1_1") (pintype "passive"))
      (node (ref "C17") (pin "1") (pinfunction "1_1") (pintype "passive"))
      (node (ref "C18") (pin "1") (pinfunction "1_1") (pintype "passive"))
      (node (ref "C19") (pin "2") (pinfunction "2_2") (pintype "passive"))
      (node (ref "C20") (pin "2") (pinfunction "2_2") (pintype "passive"))
      (node (ref "C21") (pin "1") (pinfunction "1_1") (pintype "passive"))
      (node (ref "C22") (pin "2") (pinfunction "2_2") (pintype "passive"))
      (node (ref "C26") (pin "2") (pinfunction "2_2") (pintype "passive"))
      (node (ref "C28") (pin "1") (pinfunction "1_1") (pintype "passive"))
      (node (ref "C30") (pin "1") (pinfunction "1_1") (pintype "passive"))
      (node (ref "C31") (pin "2") (pinfunction "2_2") (pintype "passive"))
      (node (ref "C32") (pin "2") (pinfunction "2_2") (pintype "passive"))
      (node (ref "C33") (pin "1") (pinfunction "1_1") (pintype "passive"))
      (node (ref "C35") (pin "1") (pinfunction "1_1") (pintype "passive"))
      (node (ref "C36") (pin "1") (pinfunction "1_1") (pintype "passive"))
      (node (ref "C37") (pin "2") (pinfunction "2_2") (pintype "passive"))
      (node (ref "C40") (pin "2") (pinfunction "2_2") (pintype "passive"))
      (node (ref "C41") (pin "1") (pinfunction "1_1") (pintype "passive"))
      (node (ref "C42") (pin "2") (pinfunction "2_2") (pintype "passive"))
      (node (ref "C43") (pin "1") (pinfunction "1_1") (pintype "passive"))
      (node (ref "C88") (pin "1") (pinfunction "1_1") (pintype "passive"))
      (node (ref "P1") (pin "2") (pinfunction "Y_2") (pintype "passive"))
      (node (ref "P10") (pin "97") (pinfunction "97_97") (pintype "passive"))
      (node (ref "P10") (pin "98") (pinfunction "98_98") (pintype "passive"))
      (node (ref "P10") (pin "A2") (pinfunction "A2_A2") (pintype "passive"))
      (node (ref "P10") (pin "A24") (pinfunction "A24_A24") (pintype "passive"))
      (node (ref "P10") (pin "A29") (pinfunction "A29_A29") (pintype "passive"))
      (node (ref "P10") (pin "A31") (pinfunction "A31_A31") (pintype "passive"))
      (node (ref "P10") (pin "B2") (pinfunction "B2_B2") (pintype "passive"))
      (node (ref "P10") (pin "B24") (pinfunction "B24_B24") (pintype "passive"))
      (node (ref "P10") (pin "B29") (pinfunction "B29_B29") (pintype "passive"))
      (node (ref "P10") (pin "B31") (pinfunction "B31_B31") (pintype "passive"))
      (node (ref "P10") (pin "C2") (pinfunction "C2_C2") (pintype "passive"))
      (node (ref "P10") (pin "C24") (pinfunction "C24_C24") (pintype "passive"))
      (node (ref "P10") (pin "C29") (pinfunction "C29_C29") (pintype "passive"))
      (node (ref "P10") (pin "C31") (pinfunction "C31_C31") (pintype "passive"))
      (node (ref "P2") (pin "2") (pinfunction "Y_2") (pintype "passive"))
      (node (ref "P3") (pin "5") (pinfunction "5_5") (pintype "passive"))
      (node (ref "P4") (pin "5") (pinfunction "5_5") (pintype "passive"))
      (node (ref "R13") (pin "1") (pinfunction "1_1") (pintype "passive"))
      (node (ref "R19") (pin "1") (pinfunction "1_1") (pintype "passive"))
      (node (ref "R25") (pin "1") (pinfunction "1_1") (pintype "passive"))
      (node (ref "R28") (pin "2") (pinfunction "2_2") (pintype "passive"))
      (node (ref "R30") (pin "2") (pinfunction "2_2") (pintype "passive"))
      (node (ref "R31") (pin "2") (pinfunction "2_2") (pintype "passive"))
      (node (ref "R32") (pin "2") (pinfunction "2_2") (pintype "passive"))
      (node (ref "R33") (pin "2") (pinfunction "2_2") (pintype "passive"))
      (node (ref "R34") (pin "2") (pinfunction "2_2") (pintype "passive"))
      (node (ref "R35") (pin "2") (pinfunction "2_2") (pintype "passive"))
      (node (ref "R36") (pin "2") (pinfunction "2_2") (pintype "passive"))
      (node (ref "R37") (pin "2") (pinfunction "2_2") (pintype "passive"))
      (node (ref "R38") (pin "2") (pinfunction "2_2") (pintype "passive"))
      (node (ref "R39") (pin "2") (pinfunction "2_2") (pintype "passive"))
      (node (ref "R40") (pin "2") (pinfunction "2_2") (pintype "passive"))
      (node (ref "R41") (pin "2") (pinfunction "2_2") (pintype "passive"))
      (node (ref "R42") (pin "2") (pinfunction "2_2") (pintype "passive"))
      (node (ref "R43") (pin "2") (pinfunction "2_2") (pintype "passive"))
      (node (ref "R44") (pin "2") (pinfunction "2_2") (pintype "passive"))
      (node (ref "R45") (pin "2") (pinfunction "2_2") (pintype "passive"))
      (node (ref "R54") (pin "2") (pinfunction "2_2") (pintype "passive"))
      (node (ref "R57") (pin "CW") (pinfunction "+_CW") (pintype "passive"))
      (node (ref "S1") (pin "1") (pinfunction "1_1") (pintype "passive"))
      (node (ref "U10") (pin "3") (pinfunction "A_3") (pintype "passive"))
      (node (ref "U11") (pin "2") (pinfunction "K_2") (pintype "passive"))
      (node (ref "U23") (pin "7") (pinfunction "GND_7") (pintype "power_in"))
      (node (ref "U8") (pin "2") (pinfunction "AVSS_2") (pintype "power_in"))
      (node (ref "U8") (pin "29") (pinfunction "AVSS_29") (pintype "power_in"))
      (node (ref "U8") (pin "31") (pinfunction "SENSE_31") (pintype "input"))
      (node (ref "U8") (pin "33") (pinfunction "REFCOM_33") (pintype "power_in"))
      (node (ref "U9") (pin "3") (pinfunction "IN+_3") (pintype "input"))
    )
    (net (code "72") (name "DGND") (class "Default")
      (node (ref "C38") (pin "1") (pinfunction "1_1") (pintype "passive"))
      (node (ref "C39") (pin "1") (pinfunction "1_1") (pintype "passive"))
      (node (ref "C44") (pin "2") (pinfunction "2_2") (pintype "passive"))
      (node (ref "C45") (pin "2") (pinfunction "2_2") (pintype "passive"))
      (node (ref "J2") (pin "1") (pinfunction "1_1") (pintype "passive"))
      (node (ref "R28") (pin "1") (pinfunction "1_1") (pintype "passive"))
      (node (ref "U12") (pin "1") (pinfunction "GND_1") (pintype "power_in"))
      (node (ref "U12") (pin "3") (pinfunction "NC_3") (pintype "passive"))
      (node (ref "U12") (pin "4") (pinfunction "NC_4") (pintype "passive"))
      (node (ref "U12") (pin "5") (pinfunction "NC_5") (pintype "passive"))
      (node (ref "U12") (pin "6") (pinfunction "NC_6") (pintype "passive"))
      (node (ref "U5") (pin "1") (pinfunction "~{OE}_1") (pintype "input"))
      (node (ref "U5") (pin "10") (pinfunction "GND_10") (pintype "power_in"))
      (node (ref "U6") (pin "1") (pinfunction "~{OE}_1") (pintype "input"))
      (node (ref "U6") (pin "10") (pinfunction "GND_10") (pintype "power_in"))
      (node (ref "U8") (pin "1") (pinfunction "DVSS_1") (pintype "power_in"))
      (node (ref "U8") (pin "5") (pinfunction "DRVSS_5") (pintype "power_in"))
      (node (ref "VR2") (pin "1") (pinfunction "GND_1") (pintype "passive"))
    )
    (net (code "73") (name "Net-(C34-Pad1)") (class "Default")
      (node (ref "C34") (pin "1") (pinfunction "1_1") (pintype "passive"))
      (node (ref "R23") (pin "2") (pinfunction "2_2") (pintype "passive"))
      (node (ref "R24") (pin "1") (pinfunction "1_1") (pintype "passive"))
    )
    (net (code "74") (name "Net-(D1-K)") (class "Default")
      (node (ref "C34") (pin "2") (pinfunction "2_2") (pintype "passive"))
      (node (ref "D1") (pin "3") (pinfunction "K_3") (pintype "passive"))
      (node (ref "R20") (pin "1") (pinfunction "1_1") (pintype "passive"))
      (node (ref "R25") (pin "2") (pinfunction "2_2") (pintype "passive"))
      (node (ref "U9") (pin "6") (pinfunction "IN-_6") (pintype "input"))
      (node (ref "U9") (pin "7") (pinfunction "OUT_7") (pintype "output"))
    )
    (net (code "75") (name "Net-(D2-PadK)") (class "Default")
      (node (ref "D2") (pin "K") (pinfunction "K_K") (pintype "passive"))
      (node (ref "R30") (pin "1") (pinfunction "1_1") (pintype "passive"))
    )
    (net (code "76") (name "Net-(D3-PadK)") (class "Default")
      (node (ref "D3") (pin "K") (pinfunction "K_K") (pintype "passive"))
      (node (ref "R31") (pin "1") (pinfunction "1_1") (pintype "passive"))
    )
    (net (code "77") (name "Net-(D4-PadK)") (class "Default")
      (node (ref "D4") (pin "K") (pinfunction "K_K") (pintype "passive"))
      (node (ref "R32") (pin "1") (pinfunction "1_1") (pintype "passive"))
    )
    (net (code "78") (name "Net-(D5-PadK)") (class "Default")
      (node (ref "D5") (pin "K") (pinfunction "K_K") (pintype "passive"))
      (node (ref "R33") (pin "1") (pinfunction "1_1") (pintype "passive"))
    )
    (net (code "79") (name "Net-(D6-PadK)") (class "Default")
      (node (ref "D6") (pin "K") (pinfunction "K_K") (pintype "passive"))
      (node (ref "R34") (pin "1") (pinfunction "1_1") (pintype "passive"))
    )
    (net (code "80") (name "Net-(D7-PadK)") (class "Default")
      (node (ref "D7") (pin "K") (pinfunction "K_K") (pintype "passive"))
      (node (ref "R35") (pin "1") (pinfunction "1_1") (pintype "passive"))
    )
    (net (code "81") (name "Net-(D8-PadK)") (class "Default")
      (node (ref "D8") (pin "K") (pinfunction "K_K") (pintype "passive"))
      (node (ref "R36") (pin "1") (pinfunction "1_1") (pintype "passive"))
    )
    (net (code "82") (name "Net-(D9-PadK)") (class "Default")
      (node (ref "D9") (pin "K") (pinfunction "K_K") (pintype "passive"))
      (node (ref "R37") (pin "1") (pinfunction "1_1") (pintype "passive"))
    )
    (net (code "83") (name "Net-(D10-PadK)") (class "Default")
      (node (ref "D10") (pin "K") (pinfunction "K_K") (pintype "passive"))
      (node (ref "R38") (pin "1") (pinfunction "1_1") (pintype "passive"))
    )
    (net (code "84") (name "Net-(D11-PadK)") (class "Default")
      (node (ref "D11") (pin "K") (pinfunction "K_K") (pintype "passive"))
      (node (ref "R39") (pin "1") (pinfunction "1_1") (pintype "passive"))
    )
    (net (code "85") (name "Net-(D12-PadK)") (class "Default")
      (node (ref "D12") (pin "K") (pinfunction "K_K") (pintype "passive"))
      (node (ref "R40") (pin "1") (pinfunction "1_1") (pintype "passive"))
    )
    (net (code "86") (name "Net-(D13-PadK)") (class "Default")
      (node (ref "D13") (pin "K") (pinfunction "K_K") (pintype "passive"))
      (node (ref "R41") (pin "1") (pinfunction "1_1") (pintype "passive"))
    )
    (net (code "87") (name "Net-(D14-PadK)") (class "Default")
      (node (ref "D14") (pin "K") (pinfunction "K_K") (pintype "passive"))
      (node (ref "R42") (pin "1") (pinfunction "1_1") (pintype "passive"))
    )
    (net (code "88") (name "Net-(D15-PadK)") (class "Default")
      (node (ref "D15") (pin "K") (pinfunction "K_K") (pintype "passive"))
      (node (ref "R43") (pin "1") (pinfunction "1_1") (pintype "passive"))
    )
    (net (code "89") (name "Net-(D16-PadK)") (class "Default")
      (node (ref "D16") (pin "K") (pinfunction "K_K") (pintype "passive"))
      (node (ref "R44") (pin "1") (pinfunction "1_1") (pintype "passive"))
    )
    (net (code "90") (name "Net-(D17-PadK)") (class "Default")
      (node (ref "D17") (pin "K") (pinfunction "K_K") (pintype "passive"))
      (node (ref "R45") (pin "1") (pinfunction "1_1") (pintype "passive"))
    )
    (net (code "91") (name "Net-(R18-Pad1)") (class "Default")
      (node (ref "R18") (pin "1") (pinfunction "1_1") (pintype "passive"))
      (node (ref "R19") (pin "2") (pinfunction "2_2") (pintype "passive"))
    )
    (net (code "92") (name "Net-(R21-+)") (class "Default")
      (node (ref "R21") (pin "CW") (pinfunction "+_CW") (pintype "passive"))
      (node (ref "R22") (pin "2") (pinfunction "2_2") (pintype "passive"))
      (node (ref "U9") (pin "2") (pinfunction "IN-_2") (pintype "input"))
    )
    (net (code "93") (name "Net-(R21--)") (class "Default")
      (node (ref "R21") (pin "CCW") (pinfunction "-_CCW") (pintype "passive"))
      (node (ref "R21") (pin "W") (pinfunction "W_W") (pintype "passive"))
      (node (ref "R23") (pin "1") (pinfunction "1_1") (pintype "passive"))
      (node (ref "U9") (pin "1") (pinfunction "OUT_1") (pintype "output"))
    )
    (net (code "94") (name "Net-(R74-Pad1)") (class "Default")
      (node (ref "R74") (pin "1") (pinfunction "1_1") (pintype "passive"))
      (node (ref "S1") (pin "2") (pinfunction "2_2") (pintype "passive"))
    )
    (net (code "95") (name "Net-(U5-Q1)") (class "Default")
      (node (ref "D2") (pin "A") (pinfunction "A_A") (pintype "passive"))
      (node (ref "U5") (pin "19") (pinfunction "Q1_19") (pintype "tri_state"))
    )
    (net (code "96") (name "Net-(U5-Q2)") (class "Default")
      (node (ref "D3") (pin "A") (pinfunction "A_A") (pintype "passive"))
      (node (ref "U5") (pin "18") (pinfunction "Q2_18") (pintype "tri_state"))
    )
    (net (code "97") (name "Net-(U5-Q3)") (class "Default")
      (node (ref "D4") (pin "A") (pinfunction "A_A") (pintype "passive"))
      (node (ref "U5") (pin "17") (pinfunction "Q3_17") (pintype "tri_state"))
    )
    (net (code "98") (name "Net-(U5-Q4)") (class "Default")
      (node (ref "D5") (pin "A") (pinfunction "A_A") (pintype "passive"))
      (node (ref "U5") (pin "16") (pinfunction "Q4_16") (pintype "tri_state"))
    )
    (net (code "99") (name "Net-(U5-Q5)") (class "Default")
      (node (ref "D6") (pin "A") (pinfunction "A_A") (pintype "passive"))
      (node (ref "U5") (pin "15") (pinfunction "Q5_15") (pintype "tri_state"))
    )
    (net (code "100") (name "Net-(U5-Q6)") (class "Default")
      (node (ref "D7") (pin "A") (pinfunction "A_A") (pintype "passive"))
      (node (ref "U5") (pin "14") (pinfunction "Q6_14") (pintype "tri_state"))
    )
    (net (code "101") (name "Net-(U5-Q7)") (class "Default")
      (node (ref "D8") (pin "A") (pinfunction "A_A") (pintype "passive"))
      (node (ref "U5") (pin "13") (pinfunction "Q7_13") (pintype "tri_state"))
    )
    (net (code "102") (name "Net-(U5-Q8)") (class "Default")
      (node (ref "D9") (pin "A") (pinfunction "A_A") (pintype "passive"))
      (node (ref "U5") (pin "12") (pinfunction "Q8_12") (pintype "tri_state"))
    )
    (net (code "103") (name "Net-(U6-Q1)") (class "Default")
      (node (ref "D10") (pin "A") (pinfunction "A_A") (pintype "passive"))
      (node (ref "U6") (pin "19") (pinfunction "Q1_19") (pintype "tri_state"))
    )
    (net (code "104") (name "Net-(U6-Q2)") (class "Default")
      (node (ref "D11") (pin "A") (pinfunction "A_A") (pintype "passive"))
      (node (ref "U6") (pin "18") (pinfunction "Q2_18") (pintype "tri_state"))
    )
    (net (code "105") (name "Net-(U6-Q3)") (class "Default")
      (node (ref "D12") (pin "A") (pinfunction "A_A") (pintype "passive"))
      (node (ref "U6") (pin "17") (pinfunction "Q3_17") (pintype "tri_state"))
    )
    (net (code "106") (name "Net-(U6-Q4)") (class "Default")
      (node (ref "D13") (pin "A") (pinfunction "A_A") (pintype "passive"))
      (node (ref "U6") (pin "16") (pinfunction "Q4_16") (pintype "tri_state"))
    )
    (net (code "107") (name "Net-(U6-Q5)") (class "Default")
      (node (ref "D14") (pin "A") (pinfunction "A_A") (pintype "passive"))
      (node (ref "U6") (pin "15") (pinfunction "Q5_15") (pintype "tri_state"))
    )
    (net (code "108") (name "Net-(U6-Q6)") (class "Default")
      (node (ref "D15") (pin "A") (pinfunction "A_A") (pintype "passive"))
      (node (ref "U6") (pin "14") (pinfunction "Q6_14") (pintype "tri_state"))
    )
    (net (code "109") (name "Net-(U6-Q7)") (class "Default")
      (node (ref "D16") (pin "A") (pinfunction "A_A") (pintype "passive"))
      (node (ref "U6") (pin "13") (pinfunction "Q7_13") (pintype "tri_state"))
    )
    (net (code "110") (name "Net-(U6-Q8)") (class "Default")
      (node (ref "D17") (pin "A") (pinfunction "A_A") (pintype "passive"))
      (node (ref "U6") (pin "12") (pinfunction "Q8_12") (pintype "tri_state"))
    )
    (net (code "111") (name "Net-(U7-+IN)") (class "Default")
      (node (ref "C25") (pin "1") (pinfunction "1_1") (pintype "passive"))
      (node (ref "R15") (pin "1") (pinfunction "1_1") (pintype "passive"))
      (node (ref "R20") (pin "2") (pinfunction "2_2") (pintype "passive"))
      (node (ref "U7") (pin "8") (pinfunction "+IN_8") (pintype "passive"))
    )
    (net (code "112") (name "Net-(U7--IN)") (class "Default")
      (node (ref "C24") (pin "1") (pinfunction "1_1") (pintype "passive"))
      (node (ref "R14") (pin "1") (pinfunction "1_1") (pintype "passive"))
      (node (ref "R18") (pin "2") (pinfunction "2_2") (pintype "passive"))
      (node (ref "U7") (pin "1") (pinfunction "-IN_1") (pintype "passive"))
    )
    (net (code "113") (name "Net-(U7-VCOM)") (class "Default")
      (node (ref "C28") (pin "2") (pinfunction "2_2") (pintype "passive"))
      (node (ref "U7") (pin "2") (pinfunction "VCOM_2") (pintype "passive"))
      (node (ref "U8") (pin "39") (pinfunction "CML_39") (pintype "power_in"))
    )
    (net (code "114") (name "Net-(U8-BIAS)") (class "Default")
      (node (ref "R13") (pin "2") (pinfunction "2_2") (pintype "passive"))
      (node (ref "U8") (pin "35") (pinfunction "BIAS_35") (pintype "passive"))
    )
    (net (code "115") (name "Net-(U8-CAPB)") (class "Default")
      (node (ref "C27") (pin "2") (pinfunction "2_2") (pintype "passive"))
      (node (ref "C29") (pin "1") (pinfunction "1_1") (pintype "passive"))
      (node (ref "C31") (pin "1") (pinfunction "1_1") (pintype "passive"))
      (node (ref "U8") (pin "36") (pinfunction "CAPB_36") (pintype "passive"))
    )
    (net (code "116") (name "Net-(U8-CAPT)") (class "Default")
      (node (ref "C26") (pin "1") (pinfunction "1_1") (pintype "passive"))
      (node (ref "C27") (pin "1") (pinfunction "1_1") (pintype "passive"))
      (node (ref "C29") (pin "2") (pinfunction "2_2") (pintype "passive"))
      (node (ref "U8") (pin "37") (pinfunction "CAPT_37") (pintype "passive"))
    )
    (net (code "117") (name "Net-(U8-VREF)") (class "Default")
      (node (ref "C32") (pin "1") (pinfunction "1_1") (pintype "passive"))
      (node (ref "C33") (pin "2") (pinfunction "2_2") (pintype "passive"))
      (node (ref "U8") (pin "32") (pinfunction "VREF_32") (pintype "bidirectional"))
    )
    (net (code "118") (name "Net-(U9B-IN+)") (class "Default")
      (node (ref "C35") (pin "2") (pinfunction "2_2") (pintype "passive"))
      (node (ref "R24") (pin "2") (pinfunction "2_2") (pintype "passive"))
      (node (ref "U9") (pin "5") (pinfunction "IN+_5") (pintype "input"))
    )
    (net (code "119") (name "Net-(U21-ADJ)") (class "Default")
      (node (ref "R54") (pin "1") (pinfunction "1_1") (pintype "passive"))
      (node (ref "R56") (pin "2") (pinfunction "2_2") (pintype "passive"))
      (node (ref "U21") (pin "1") (pinfunction "ADJ_1") (pintype "input"))
    )
    (net (code "120") (name "Net-(U23C-A)") (class "Default")
      (node (ref "C88") (pin "2") (pinfunction "2_2") (pintype "passive"))
      (node (ref "R73") (pin "2") (pinfunction "2_2") (pintype "passive"))
      (node (ref "R74") (pin "2") (pinfunction "2_2") (pintype "passive"))
      (node (ref "U23") (pin "5") (pinfunction "A_5") (pintype "input"))
    )
    (net (code "121") (name "Net-(U23C-Y)") (class "Default")
      (node (ref "R75") (pin "1") (pinfunction "1_1") (pintype "passive"))
      (node (ref "U23") (pin "6") (pinfunction "Y_6") (pintype "output"))
    )
    (net (code "122") (name "VCCO") (class "Default")
      (node (ref "C45") (pin "1") (pinfunction "1_1") (pintype "passive"))
      (node (ref "P3") (pin "6") (pinfunction "6_6") (pintype "passive"))
      (node (ref "P4") (pin "6") (pinfunction "6_6") (pintype "passive"))
      (node (ref "R29") (pin "2") (pinfunction "2_2") (pintype "passive"))
      (node (ref "R73") (pin "1") (pinfunction "1_1") (pintype "passive"))
      (node (ref "U23") (pin "14") (pinfunction "VDD_14") (pintype "power_in"))
      (node (ref "U8") (pin "6") (pinfunction "DRVDD_6") (pintype "power_in"))
      (node (ref "VR2") (pin "2") (pinfunction "Vout_2") (pintype "passive"))
    )
    (net (code "123") (name "VE") (class "Default")
      (node (ref "P10") (pin "A32") (pinfunction "A32_A32") (pintype "passive"))
      (node (ref "P10") (pin "B32") (pinfunction "B32_B32") (pintype "passive"))
      (node (ref "P10") (pin "C32") (pinfunction "C32_C32") (pintype "passive"))
      (node (ref "P2") (pin "1") (pinfunction "X_1") (pintype "passive"))
      (node (ref "R57") (pin "CCW") (pinfunction "-_CCW") (pintype "passive"))
    )
    (net (code "124") (name "VO") (class "Default")
      (node (ref "P1") (pin "1") (pinfunction "X_1") (pintype "passive"))
      (node (ref "R22") (pin "1") (pinfunction "1_1") (pintype "passive"))
      (node (ref "R57") (pin "W") (pinfunction "W_W") (pintype "passive"))
    )
    (net (code "125") (name "unconnected-(P10-PadA16)") (class "Default")
      (node (ref "P10") (pin "A16") (pinfunction "A16_A16") (pintype "passive"))
    )
    (net (code "126") (name "unconnected-(P10-PadA17)") (class "Default")
      (node (ref "P10") (pin "A17") (pinfunction "A17_A17") (pintype "passive"))
    )
    (net (code "127") (name "unconnected-(P10-PadA20)") (class "Default")
      (node (ref "P10") (pin "A20") (pinfunction "A20_A20") (pintype "passive+no_connect"))
    )
    (net (code "128") (name "unconnected-(P10-PadA21)") (class "Default")
      (node (ref "P10") (pin "A21") (pinfunction "A21_A21") (pintype "passive+no_connect"))
    )
    (net (code "129") (name "unconnected-(P10-PadA22)") (class "Default")
      (node (ref "P10") (pin "A22") (pinfunction "A22_A22") (pintype "passive+no_connect"))
    )
    (net (code "130") (name "unconnected-(P10-PadA23)") (class "Default")
      (node (ref "P10") (pin "A23") (pinfunction "A23_A23") (pintype "passive"))
    )
    (net (code "131") (name "unconnected-(P10-PadA25)") (class "Default")
      (node (ref "P10") (pin "A25") (pinfunction "A25_A25") (pintype "passive+no_connect"))
    )
    (net (code "132") (name "unconnected-(P10-PadA26)") (class "Default")
      (node (ref "P10") (pin "A26") (pinfunction "A26_A26") (pintype "passive+no_connect"))
    )
    (net (code "133") (name "unconnected-(P10-PadA27)") (class "Default")
      (node (ref "P10") (pin "A27") (pinfunction "A27_A27") (pintype "passive+no_connect"))
    )
    (net (code "134") (name "unconnected-(P10-PadA28)") (class "Default")
      (node (ref "P10") (pin "A28") (pinfunction "A28_A28") (pintype "passive+no_connect"))
    )
    (net (code "135") (name "unconnected-(P10-PadB4)") (class "Default")
      (node (ref "P10") (pin "B4") (pinfunction "B4_B4") (pintype "passive+no_connect"))
    )
    (net (code "136") (name "unconnected-(P10-PadB5)") (class "Default")
      (node (ref "P10") (pin "B5") (pinfunction "B5_B5") (pintype "passive+no_connect"))
    )
    (net (code "137") (name "unconnected-(P10-PadB6)") (class "Default")
      (node (ref "P10") (pin "B6") (pinfunction "B6_B6") (pintype "passive+no_connect"))
    )
    (net (code "138") (name "unconnected-(P10-PadB7)") (class "Default")
      (node (ref "P10") (pin "B7") (pinfunction "B7_B7") (pintype "passive+no_connect"))
    )
    (net (code "139") (name "unconnected-(P10-PadB8)") (class "Default")
      (node (ref "P10") (pin "B8") (pinfunction "B8_B8") (pintype "passive+no_connect"))
    )
    (net (code "140") (name "unconnected-(P10-PadB9)") (class "Default")
      (node (ref "P10") (pin "B9") (pinfunction "B9_B9") (pintype "passive+no_connect"))
    )
    (net (code "141") (name "unconnected-(P10-PadB10)") (class "Default")
      (node (ref "P10") (pin "B10") (pinfunction "B10_B10") (pintype "passive+no_connect"))
    )
    (net (code "142") (name "unconnected-(P10-PadB11)") (class "Default")
      (node (ref "P10") (pin "B11") (pinfunction "B11_B11") (pintype "passive+no_connect"))
    )
    (net (code "143") (name "unconnected-(P10-PadB16)") (class "Default")
      (node (ref "P10") (pin "B16") (pinfunction "B16_B16") (pintype "passive"))
    )
    (net (code "144") (name "unconnected-(P10-PadB17)") (class "Default")
      (node (ref "P10") (pin "B17") (pinfunction "B17_B17") (pintype "passive"))
    )
    (net (code "145") (name "unconnected-(P10-PadB18)") (class "Default")
      (node (ref "P10") (pin "B18") (pinfunction "B18_B18") (pintype "passive"))
    )
    (net (code "146") (name "unconnected-(P10-PadB19)") (class "Default")
      (node (ref "P10") (pin "B19") (pinfunction "B19_B19") (pintype "passive"))
    )
    (net (code "147") (name "unconnected-(P10-PadB20)") (class "Default")
      (node (ref "P10") (pin "B20") (pinfunction "B20_B20") (pintype "passive"))
    )
    (net (code "148") (name "unconnected-(P10-PadB21)") (class "Default")
      (node (ref "P10") (pin "B21") (pinfunction "B21_B21") (pintype "passive"))
    )
    (net (code "149") (name "unconnected-(P10-PadB22)") (class "Default")
      (node (ref "P10") (pin "B22") (pinfunction "B22_B22") (pintype "passive"))
    )
    (net (code "150") (name "unconnected-(P10-PadB23)") (class "Default")
      (node (ref "P10") (pin "B23") (pinfunction "B23_B23") (pintype "passive"))
    )
    (net (code "151") (name "unconnected-(P10-PadB25)") (class "Default")
      (node (ref "P10") (pin "B25") (pinfunction "B25_B25") (pintype "passive+no_connect"))
    )
    (net (code "152") (name "unconnected-(P10-PadB26)") (class "Default")
      (node (ref "P10") (pin "B26") (pinfunction "B26_B26") (pintype "passive+no_connect"))
    )
    (net (code "153") (name "unconnected-(P10-PadB27)") (class "Default")
      (node (ref "P10") (pin "B27") (pinfunction "B27_B27") (pintype "passive+no_connect"))
    )
    (net (code "154") (name "unconnected-(P10-PadB28)") (class "Default")
      (node (ref "P10") (pin "B28") (pinfunction "B28_B28") (pintype "passive+no_connect"))
    )
    (net (code "155") (name "unconnected-(P10-PadC20)") (class "Default")
      (node (ref "P10") (pin "C20") (pinfunction "C20_C20") (pintype "passive+no_connect"))
    )
    (net (code "156") (name "unconnected-(P10-PadC21)") (class "Default")
      (node (ref "P10") (pin "C21") (pinfunction "C21_C21") (pintype "passive+no_connect"))
    )
    (net (code "157") (name "unconnected-(P10-PadC22)") (class "Default")
      (node (ref "P10") (pin "C22") (pinfunction "C22_C22") (pintype "passive+no_connect"))
    )
    (net (code "158") (name "unconnected-(P10-PadC23)") (class "Default")
      (node (ref "P10") (pin "C23") (pinfunction "C23_C23") (pintype "passive"))
    )
    (net (code "159") (name "unconnected-(P10-PadC25)") (class "Default")
      (node (ref "P10") (pin "C25") (pinfunction "C25_C25") (pintype "passive+no_connect"))
    )
    (net (code "160") (name "unconnected-(P10-PadC26)") (class "Default")
      (node (ref "P10") (pin "C26") (pinfunction "C26_C26") (pintype "passive+no_connect"))
    )
    (net (code "161") (name "unconnected-(P10-PadC27)") (class "Default")
      (node (ref "P10") (pin "C27") (pinfunction "C27_C27") (pintype "passive+no_connect"))
    )
    (net (code "162") (name "unconnected-(P10-PadC28)") (class "Default")
      (node (ref "P10") (pin "C28") (pinfunction "C28_C28") (pintype "passive+no_connect"))
    )
    (net (code "163") (name "unconnected-(U7-NC-Pad7)") (class "Default")
      (node (ref "U7") (pin "7") (pinfunction "NC_7") (pintype "passive"))
    )
    (net (code "164") (name "unconnected-(U8-NC-Pad8)") (class "Default")
      (node (ref "U8") (pin "8") (pinfunction "NC_8") (pintype "passive+no_connect"))
    )
    (net (code "165") (name "unconnected-(U8-NC-Pad9)") (class "Default")
      (node (ref "U8") (pin "9") (pinfunction "NC_9") (pintype "passive+no_connect"))
    )
    (net (code "166") (name "unconnected-(U8-NC-Pad10)") (class "Default")
      (node (ref "U8") (pin "10") (pinfunction "NC_10") (pintype "passive+no_connect"))
    )
    (net (code "167") (name "unconnected-(U8-NC-Pad26)") (class "Default")
      (node (ref "U8") (pin "26") (pinfunction "NC_26") (pintype "passive+no_connect"))
    )
    (net (code "168") (name "unconnected-(U8-NC-Pad27)") (class "Default")
      (node (ref "U8") (pin "27") (pinfunction "NC_27") (pintype "passive+no_connect"))
    )
    (net (code "169") (name "unconnected-(U8-NC-Pad30)") (class "Default")
      (node (ref "U8") (pin "30") (pinfunction "NC_30") (pintype "passive+no_connect"))
    )
    (net (code "170") (name "unconnected-(U8-NC-Pad34)") (class "Default")
      (node (ref "U8") (pin "34") (pinfunction "NC_34") (pintype "passive+no_connect"))
    )
    (net (code "171") (name "unconnected-(U8-NC-Pad38)") (class "Default")
      (node (ref "U8") (pin "38") (pinfunction "NC_38") (pintype "passive+no_connect"))
    )
    (net (code "172") (name "unconnected-(U8-NC-Pad40)") (class "Default")
      (node (ref "U8") (pin "40") (pinfunction "NC_40") (pintype "passive+no_connect"))
    )
    (net (code "173") (name "unconnected-(U8-NC-Pad43)") (class "Default")
      (node (ref "U8") (pin "43") (pinfunction "NC_43") (pintype "passive+no_connect"))
    )
    (net (code "174") (name "unconnected-(U8-NC-Pad44)") (class "Default")
      (node (ref "U8") (pin "44") (pinfunction "NC_44") (pintype "passive+no_connect"))
    )
    (net (code "175") (name "unconnected-(U10-R-Pad1)") (class "Default")
      (node (ref "U10") (pin "1") (pinfunction "R_1") (pintype "passive"))
    )
    (net (code "176") (name "unconnected-(U11-R-Pad1)") (class "Default")
      (node (ref "U11") (pin "1") (pinfunction "R_1") (pintype "passive"))
    )
    (net (code "177") (name "unconnected-(U23D-A-Pad9)") (class "Default")
      (node (ref "U23") (pin "9") (pinfunction "A_9") (pintype "input"))
    )
    (net (code "178") (name "unconnected-(U23D-Y-Pad8)") (class "Default")
      (node (ref "U23") (pin "8") (pinfunction "Y_8") (pintype "output"))
    )
    (net (code "179") (name "unconnected-(U23E-A-Pad11)") (class "Default")
      (node (ref "U23") (pin "11") (pinfunction "A_11") (pintype "input"))
    )
    (net (code "180") (name "unconnected-(U23E-Y-Pad10)") (class "Default")
      (node (ref "U23") (pin "10") (pinfunction "Y_10") (pintype "output"))
    )
    (net (code "181") (name "unconnected-(U23F-A-Pad13)") (class "Default")
      (node (ref "U23") (pin "13") (pinfunction "A_13") (pintype "input"))
    )
    (net (code "182") (name "unconnected-(U23F-Y-Pad12)") (class "Default")
      (node (ref "U23") (pin "12") (pinfunction "Y_12") (pintype "output"))
    )
  )
)
